# F4Z6Y7PIP1H1BGX.net
KiCad netlist of a schematic drawn in EAGLE
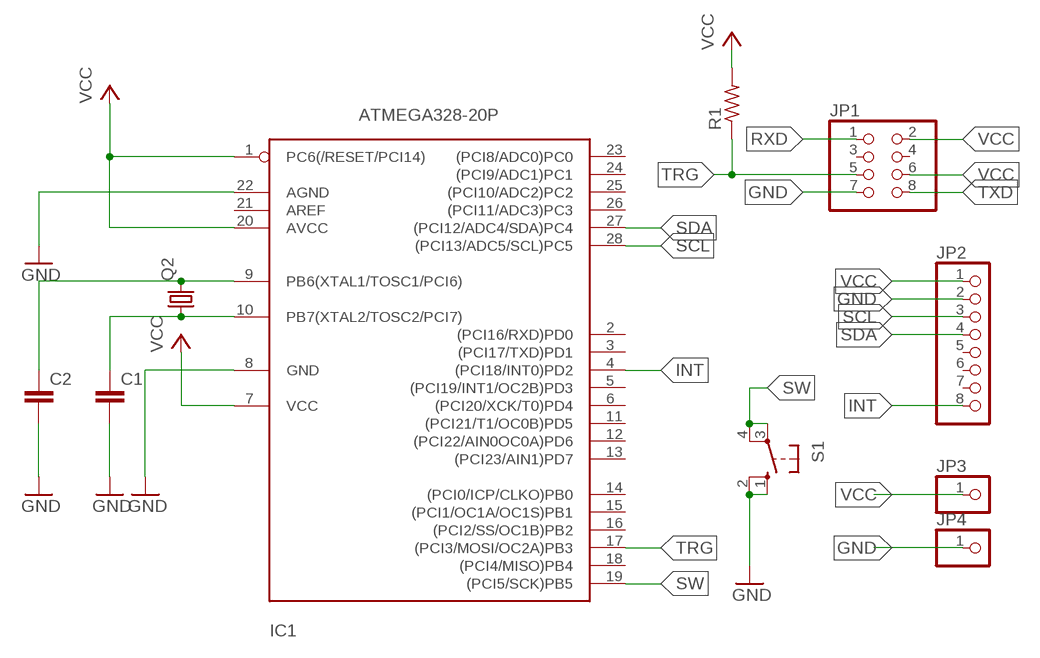
[diagram p0: schematic, sheet 1]

(export (version "E")
  (design (tool "Eeschema 10.0.6"))
  (components
    (comp (ref "C1")
      (value "C2,5-3")
      (footprint "eagle-import:C2.5-3")
      (libsource (lib "eagle-import") (part "C2,5-3"))
    )
    (comp (ref "C2")
      (value "C2,5-3")
      (footprint "eagle-import:C2.5-3")
      (libsource (lib "eagle-import") (part "C2,5-3"))
    )
    (comp (ref "IC1")
      (value "ATMEGA328-20P")
      (footprint "eagle-import:DIL28-3")
      (libsource (lib "eagle-import") (part "ATMEGA328P-20"))
    )
    (comp (ref "JP1")
      (value "PINHD-2X4")
      (footprint "eagle-import:2X04")
      (libsource (lib "eagle-import") (part "PINHD-2X4"))
    )
    (comp (ref "JP2")
      (value "PINHD-1X8/90")
      (footprint "eagle-import:1X08_90")
      (libsource (lib "eagle-import") (part "PINHD-1X8/90"))
    )
    (comp (ref "JP3")
      (value "PINHD-1X1")
      (footprint "eagle-import:1X01")
      (libsource (lib "eagle-import") (part "PINHD-1X1"))
    )
    (comp (ref "JP4")
      (value "PINHD-1X1")
      (footprint "eagle-import:1X01")
      (libsource (lib "eagle-import") (part "PINHD-1X1"))
    )
    (comp (ref "Q2")
      (value "CRYSTALHC49S")
      (footprint "eagle-import:HC49_S")
      (libsource (lib "eagle-import") (part "CRYSTALHC49S"))
    )
    (comp (ref "R1")
      (value "R-US_0204/7")
      (footprint "eagle-import:0204_7")
      (libsource (lib "eagle-import") (part "R-US_0204/7"))
    )
    (comp (ref "S1")
      (value "10-XX")
      (footprint "eagle-import:B3F-10XX")
      (fields (field (name "MPN") "B3F-1000"))
      (libsource (lib "eagle-import") (part "10-XX"))
    )
  )
  (nets
    (net (code "1") (name "GND") (class "Default")
      (node (ref "C1") (pin "2") (pinfunction "2_2") (pintype "passive"))
      (node (ref "C2") (pin "2") (pinfunction "2_2") (pintype "passive"))
      (node (ref "IC1") (pin "22") (pinfunction "AGND_22") (pintype "bidirectional"))
      (node (ref "IC1") (pin "8") (pinfunction "GND_8") (pintype "bidirectional"))
      (node (ref "JP1") (pin "7") (pinfunction "7_7") (pintype "passive"))
      (node (ref "JP2") (pin "2") (pinfunction "2_2") (pintype "passive"))
      (node (ref "JP4") (pin "1") (pinfunction "1_1") (pintype "passive"))
      (node (ref "S1") (pin "1") (pinfunction "S_1") (pintype "passive"))
      (node (ref "S1") (pin "2") (pinfunction "S1_2") (pintype "passive"))
    )
    (net (code "2") (name "INT") (class "Default")
      (node (ref "IC1") (pin "4") (pinfunction "(PCI18/INT0)PD2_4") (pintype "bidirectional"))
      (node (ref "JP2") (pin "8") (pinfunction "8_8") (pintype "passive"))
    )
    (net (code "3") (name "Net-(IC1-PB6(XTAL1{slash}TOSC1{slash}PCI6))") (class "Default")
      (node (ref "C2") (pin "1") (pinfunction "1_1") (pintype "passive"))
      (node (ref "IC1") (pin "9") (pinfunction "PB6(XTAL1/TOSC1/PCI6)_9") (pintype "bidirectional"))
      (node (ref "Q2") (pin "2") (pinfunction "2_2") (pintype "passive"))
    )
    (net (code "4") (name "Net-(IC1-PB7(XTAL2{slash}TOSC2{slash}PCI7))") (class "Default")
      (node (ref "C1") (pin "1") (pinfunction "1_1") (pintype "passive"))
      (node (ref "IC1") (pin "10") (pinfunction "PB7(XTAL2/TOSC2/PCI7)_10") (pintype "bidirectional"))
      (node (ref "Q2") (pin "1") (pinfunction "1_1") (pintype "passive"))
    )
    (net (code "5") (name "RXD") (class "Default")
      (node (ref "JP1") (pin "1") (pinfunction "1_1") (pintype "passive"))
    )
    (net (code "6") (name "SCL") (class "Default")
      (node (ref "IC1") (pin "28") (pinfunction "(PCI13/ADC5/SCL)PC5_28") (pintype "bidirectional"))
      (node (ref "JP2") (pin "3") (pinfunction "3_3") (pintype "passive"))
    )
    (net (code "7") (name "SDA") (class "Default")
      (node (ref "IC1") (pin "27") (pinfunction "(PCI12/ADC4/SDA)PC4_27") (pintype "bidirectional"))
      (node (ref "JP2") (pin "4") (pinfunction "4_4") (pintype "passive"))
    )
    (net (code "8") (name "SW") (class "Default")
      (node (ref "IC1") (pin "19") (pinfunction "(PCI5/SCK)PB5_19") (pintype "bidirectional"))
      (node (ref "S1") (pin "3") (pinfunction "P_3") (pintype "passive"))
      (node (ref "S1") (pin "4") (pinfunction "P1_4") (pintype "passive"))
    )
    (net (code "9") (name "TRG") (class "Default")
      (node (ref "IC1") (pin "17") (pinfunction "(PCI3/MOSI/OC2A)PB3_17") (pintype "bidirectional"))
      (node (ref "JP1") (pin "5") (pinfunction "5_5") (pintype "passive"))
      (node (ref "R1") (pin "1") (pinfunction "1_1") (pintype "passive"))
    )
    (net (code "10") (name "TXD") (class "Default")
      (node (ref "JP1") (pin "8") (pinfunction "8_8") (pintype "passive"))
    )
    (net (code "11") (name "VCC") (class "Default")
      (node (ref "IC1") (pin "1") (pinfunction "PC6(/RESET/PCI14)_1") (pintype "bidirectional"))
      (node (ref "IC1") (pin "20") (pinfunction "AVCC_20") (pintype "bidirectional"))
      (node (ref "IC1") (pin "7") (pinfunction "VCC_7") (pintype "bidirectional"))
      (node (ref "JP1") (pin "2") (pinfunction "2_2") (pintype "passive"))
      (node (ref "JP1") (pin "6") (pinfunction "6_6") (pintype "passive"))
      (node (ref "JP2") (pin "1") (pinfunction "1_1") (pintype "passive"))
      (node (ref "JP3") (pin "1") (pinfunction "1_1") (pintype "passive"))
      (node (ref "R1") (pin "2") (pinfunction "2_2") (pintype "passive"))
    )
    (net (code "12") (name "unconnected-(IC1-(PCI0{slash}ICP{slash}CLKO)PB0-Pad14)") (class "Default")
      (node (ref "IC1") (pin "14") (pinfunction "(PCI0/ICP/CLKO)PB0_14") (pintype "bidirectional"))
    )
    (net (code "13") (name "unconnected-(IC1-(PCI1{slash}OC1A{slash}OC1S)PB1-Pad15)") (class "Default")
      (node (ref "IC1") (pin "15") (pinfunction "(PCI1/OC1A/OC1S)PB1_15") (pintype "bidirectional"))
    )
    (net (code "14") (name "unconnected-(IC1-(PCI2{slash}SS{slash}OC1B)PB2-Pad16)") (class "Default")
      (node (ref "IC1") (pin "16") (pinfunction "(PCI2/SS/OC1B)PB2_16") (pintype "bidirectional"))
    )
    (net (code "15") (name "unconnected-(IC1-(PCI4{slash}MISO)PB4-Pad18)") (class "Default")
      (node (ref "IC1") (pin "18") (pinfunction "(PCI4/MISO)PB4_18") (pintype "bidirectional"))
    )
    (net (code "16") (name "unconnected-(IC1-(PCI8{slash}ADC0)PC0-Pad23)") (class "Default")
      (node (ref "IC1") (pin "23") (pinfunction "(PCI8/ADC0)PC0_23") (pintype "bidirectional"))
    )
    (net (code "17") (name "unconnected-(IC1-(PCI9{slash}ADC1)PC1-Pad24)") (class "Default")
      (node (ref "IC1") (pin "24") (pinfunction "(PCI9/ADC1)PC1_24") (pintype "bidirectional"))
    )
    (net (code "18") (name "unconnected-(IC1-(PCI10{slash}ADC2)PC2-Pad25)") (class "Default")
      (node (ref "IC1") (pin "25") (pinfunction "(PCI10/ADC2)PC2_25") (pintype "bidirectional"))
    )
    (net (code "19") (name "unconnected-(IC1-(PCI11{slash}ADC3)PC3-Pad26)") (class "Default")
      (node (ref "IC1") (pin "26") (pinfunction "(PCI11/ADC3)PC3_26") (pintype "bidirectional"))
    )
    (net (code "20") (name "unconnected-(IC1-(PCI16{slash}RXD)PD0-Pad2)") (class "Default")
      (node (ref "IC1") (pin "2") (pinfunction "(PCI16/RXD)PD0_2") (pintype "bidirectional"))
    )
    (net (code "21") (name "unconnected-(IC1-(PCI17{slash}TXD)PD1-Pad3)") (class "Default")
      (node (ref "IC1") (pin "3") (pinfunction "(PCI17/TXD)PD1_3") (pintype "bidirectional"))
    )
    (net (code "22") (name "unconnected-(IC1-(PCI19{slash}INT1{slash}OC2B)PD3-Pad5)") (class "Default")
      (node (ref "IC1") (pin "5") (pinfunction "(PCI19/INT1/OC2B)PD3_5") (pintype "bidirectional"))
    )
    (net (code "23") (name "unconnected-(IC1-(PCI20{slash}XCK{slash}T0)PD4-Pad6)") (class "Default")
      (node (ref "IC1") (pin "6") (pinfunction "(PCI20/XCK/T0)PD4_6") (pintype "bidirectional"))
    )
    (net (code "24") (name "unconnected-(IC1-(PCI21{slash}T1{slash}OC0B)PD5-Pad11)") (class "Default")
      (node (ref "IC1") (pin "11") (pinfunction "(PCI21/T1/OC0B)PD5_11") (pintype "bidirectional"))
    )
    (net (code "25") (name "unconnected-(IC1-(PCI22{slash}AIN0OC0A)PD6-Pad12)") (class "Default")
      (node (ref "IC1") (pin "12") (pinfunction "(PCI22/AIN0OC0A)PD6_12") (pintype "bidirectional"))
    )
    (net (code "26") (name "unconnected-(IC1-(PCI23{slash}AIN1)PD7-Pad13)") (class "Default")
      (node (ref "IC1") (pin "13") (pinfunction "(PCI23/AIN1)PD7_13") (pintype "bidirectional"))
    )
    (net (code "27") (name "unconnected-(IC1-AREF-Pad21)") (class "Default")
      (node (ref "IC1") (pin "21") (pinfunction "AREF_21") (pintype "bidirectional"))
    )
    (net (code "28") (name "unconnected-(JP1-Pad3)") (class "Default")
      (node (ref "JP1") (pin "3") (pinfunction "3_3") (pintype "passive"))
    )
    (net (code "29") (name "unconnected-(JP1-Pad4)") (class "Default")
      (node (ref "JP1") (pin "4") (pinfunction "4_4") (pintype "passive"))
    )
    (net (code "30") (name "unconnected-(JP2-Pad5)") (class "Default")
      (node (ref "JP2") (pin "5") (pinfunction "5_5") (pintype "passive"))
    )
    (net (code "31") (name "unconnected-(JP2-Pad6)") (class "Default")
      (node (ref "JP2") (pin "6") (pinfunction "6_6") (pintype "passive"))
    )
    (net (code "32") (name "unconnected-(JP2-Pad7)") (class "Default")
      (node (ref "JP2") (pin "7") (pinfunction "7_7") (pintype "passive"))
    )
  )
)
